# SolarMonitor.net
KiCad netlist of a schematic drawn in EAGLE
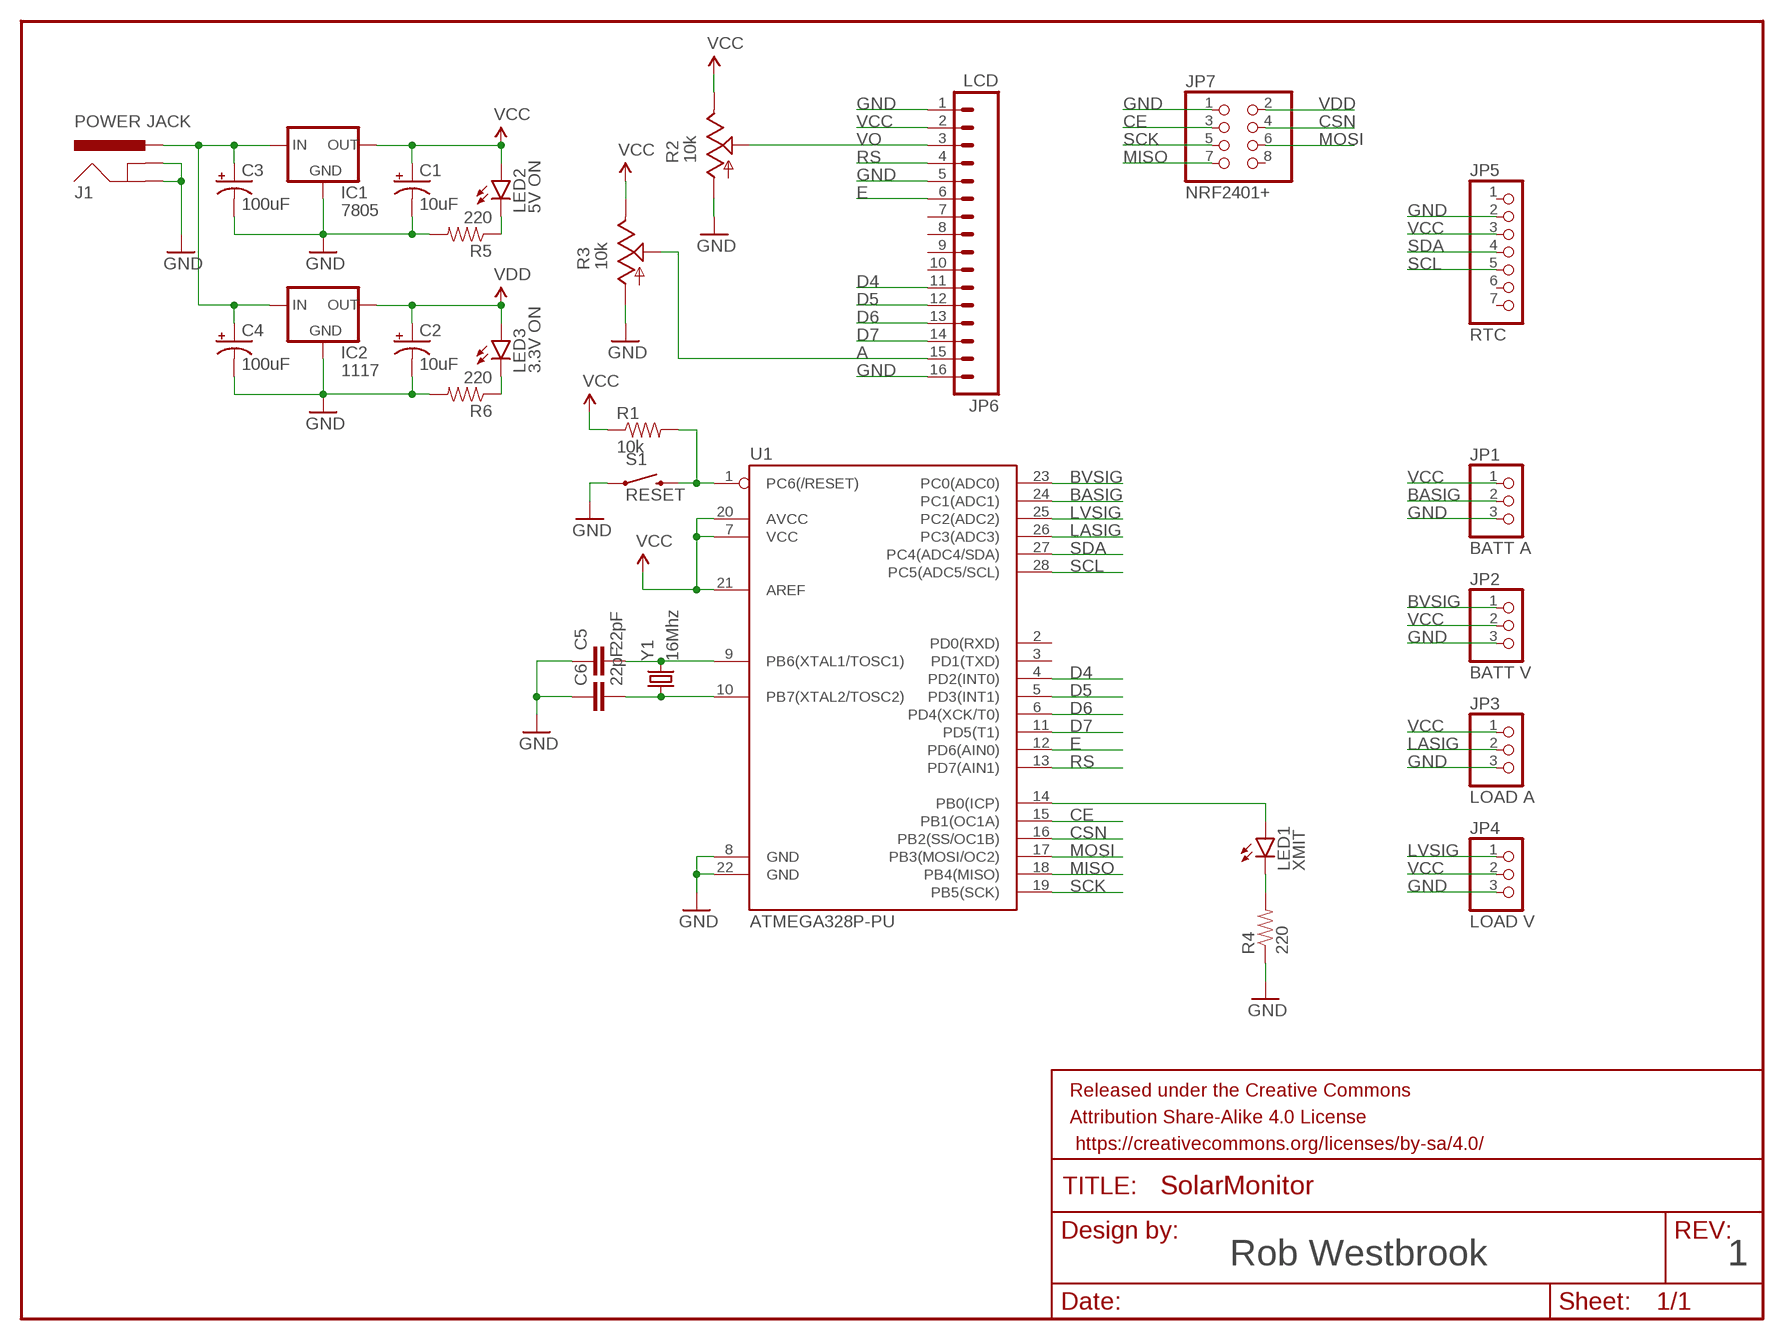
[diagram p0: schematic, sheet 1]

(export (version "E")
  (design (tool "Eeschema 10.0.6"))
  (components
    (comp (ref "C1")
      (value "10uF")
      (footprint "eagle-import:CPOL-RADIAL-100UF-25V")
      (libsource (lib "eagle-import") (part "CAP_POLPTH1"))
    )
    (comp (ref "C2")
      (value "10uF")
      (footprint "eagle-import:CPOL-RADIAL-100UF-25V")
      (libsource (lib "eagle-import") (part "CAP_POLPTH1"))
    )
    (comp (ref "C3")
      (value "100uF")
      (footprint "eagle-import:CPOL-RADIAL-10UF-25V")
      (libsource (lib "eagle-import") (part "CAP_POLPTH2"))
    )
    (comp (ref "C4")
      (value "100uF")
      (footprint "eagle-import:CPOL-RADIAL-10UF-25V")
      (libsource (lib "eagle-import") (part "CAP_POLPTH2"))
    )
    (comp (ref "C5")
      (value "22pF")
      (footprint "eagle-import:CAP-PTH-SMALLEZ")
      (libsource (lib "eagle-import") (part "CAPEZ"))
    )
    (comp (ref "C6")
      (value "22pF")
      (footprint "eagle-import:CAP-PTH-SMALLEZ")
      (libsource (lib "eagle-import") (part "CAPEZ"))
    )
    (comp (ref "FRAME1")
      (value "FRAME-LETTER")
      (footprint "eagle-import:CREATIVE_COMMONS")
      (libsource (lib "eagle-import") (part "FRAME-LETTER"))
    )
    (comp (ref "IC1")
      (value "7805")
      (footprint "eagle-import:TO-220-ALT")
      (libsource (lib "eagle-import") (part "V_REG_78XX-TO-220"))
    )
    (comp (ref "IC2")
      (value "1117")
      (footprint "eagle-import:78XXL")
      (libsource (lib "eagle-import") (part "V_REG_LD1117VXX"))
    )
    (comp (ref "J1")
      (value "POWER JACK")
      (footprint "eagle-import:POWER_JACK_PTH")
      (libsource (lib "eagle-import") (part "POWER_JACKPTH"))
    )
    (comp (ref "JP1")
      (value "BATT A")
      (footprint "eagle-import:1X03")
      (libsource (lib "eagle-import") (part "PINHD-1X3"))
    )
    (comp (ref "JP2")
      (value "BATT V")
      (footprint "eagle-import:1X03")
      (libsource (lib "eagle-import") (part "PINHD-1X3"))
    )
    (comp (ref "JP3")
      (value "LOAD A")
      (footprint "eagle-import:1X03")
      (libsource (lib "eagle-import") (part "PINHD-1X3"))
    )
    (comp (ref "JP4")
      (value "LOAD V")
      (footprint "eagle-import:1X03")
      (libsource (lib "eagle-import") (part "PINHD-1X3"))
    )
    (comp (ref "JP5")
      (value "RTC")
      (footprint "eagle-import:1X07")
      (libsource (lib "eagle-import") (part "PINHD-1X7"))
    )
    (comp (ref "JP6")
      (value "LCD")
      (footprint "eagle-import:1X16_LOCK")
      (libsource (lib "eagle-import") (part "M16LOCK"))
    )
    (comp (ref "JP7")
      (value "NRF2401+")
      (footprint "eagle-import:2X04")
      (libsource (lib "eagle-import") (part "PINHD-2X4"))
    )
    (comp (ref "LED1")
      (value "XMIT")
      (footprint "eagle-import:LED5MM")
      (libsource (lib "eagle-import") (part "LED5MM"))
    )
    (comp (ref "LED2")
      (value "5V ON")
      (footprint "eagle-import:LED5MM")
      (libsource (lib "eagle-import") (part "LED5MM"))
    )
    (comp (ref "LED3")
      (value "3.3V ON")
      (footprint "eagle-import:LED5MM")
      (libsource (lib "eagle-import") (part "LED5MM"))
    )
    (comp (ref "R1")
      (value "10k")
      (footprint "eagle-import:AXIAL-0.4")
      (libsource (lib "eagle-import") (part "RESISTORPTH-1/4W"))
    )
    (comp (ref "R2")
      (value "10k")
      (footprint "eagle-import:S64W")
      (libsource (lib "eagle-import") (part "TRIM_US-S64W"))
    )
    (comp (ref "R3")
      (value "10k")
      (footprint "eagle-import:S64W")
      (libsource (lib "eagle-import") (part "TRIM_US-S64W"))
    )
    (comp (ref "R4")
      (value "220")
      (footprint "eagle-import:AXIAL-0.4")
      (libsource (lib "eagle-import") (part "RESISTORPTH-1/4W"))
    )
    (comp (ref "R5")
      (value "220")
      (footprint "eagle-import:AXIAL-0.4")
      (libsource (lib "eagle-import") (part "RESISTORPTH-1/4W"))
    )
    (comp (ref "R6")
      (value "220")
      (footprint "eagle-import:AXIAL-0.4")
      (libsource (lib "eagle-import") (part "RESISTORPTH-1/4W"))
    )
    (comp (ref "S1")
      (value "RESET")
      (footprint "eagle-import:TACTILE-PTH")
      (libsource (lib "eagle-import") (part "SWITCH-MOMENTARY-2PTH"))
    )
    (comp (ref "U1")
      (value "ATMEGA328P-PU")
      (footprint "eagle-import:DIL28-3")
      (libsource (lib "eagle-import") (part "ATMEGA328P_PDIP"))
    )
    (comp (ref "Y1")
      (value "16Mhz")
      (footprint "eagle-import:HC49US")
      (libsource (lib "eagle-import") (part "CRYSTALHC49US"))
    )
  )
  (nets
    (net (code "1") (name "/A") (class "Default")
      (node (ref "JP6") (pin "15") (pinfunction "15_15") (pintype "passive"))
      (node (ref "R3") (pin "S") (pinfunction "S_S") (pintype "passive"))
    )
    (net (code "2") (name "/BASIG") (class "Default")
      (node (ref "JP1") (pin "2") (pinfunction "2_2") (pintype "passive"))
      (node (ref "U1") (pin "24") (pinfunction "PC1(ADC1)_24") (pintype "bidirectional"))
    )
    (net (code "3") (name "/BVSIG") (class "Default")
      (node (ref "JP2") (pin "1") (pinfunction "1_1") (pintype "passive"))
      (node (ref "U1") (pin "23") (pinfunction "PC0(ADC0)_23") (pintype "bidirectional"))
    )
    (net (code "4") (name "/CE") (class "Default")
      (node (ref "JP7") (pin "3") (pinfunction "3_3") (pintype "passive"))
      (node (ref "U1") (pin "15") (pinfunction "PB1(OC1A)_15") (pintype "bidirectional"))
    )
    (net (code "5") (name "/CSN") (class "Default")
      (node (ref "JP7") (pin "4") (pinfunction "4_4") (pintype "passive"))
      (node (ref "U1") (pin "16") (pinfunction "PB2(SS/OC1B)_16") (pintype "bidirectional"))
    )
    (net (code "6") (name "/D4") (class "Default")
      (node (ref "JP6") (pin "11") (pinfunction "11_11") (pintype "passive"))
      (node (ref "U1") (pin "4") (pinfunction "PD2(INT0)_4") (pintype "bidirectional"))
    )
    (net (code "7") (name "/D5") (class "Default")
      (node (ref "JP6") (pin "12") (pinfunction "12_12") (pintype "passive"))
      (node (ref "U1") (pin "5") (pinfunction "PD3(INT1)_5") (pintype "bidirectional"))
    )
    (net (code "8") (name "/D6") (class "Default")
      (node (ref "JP6") (pin "13") (pinfunction "13_13") (pintype "passive"))
      (node (ref "U1") (pin "6") (pinfunction "PD4(XCK/T0)_6") (pintype "bidirectional"))
    )
    (net (code "9") (name "/D7") (class "Default")
      (node (ref "JP6") (pin "14") (pinfunction "14_14") (pintype "passive"))
      (node (ref "U1") (pin "11") (pinfunction "PD5(T1)_11") (pintype "bidirectional"))
    )
    (net (code "10") (name "/E") (class "Default")
      (node (ref "JP6") (pin "6") (pinfunction "6_6") (pintype "passive"))
      (node (ref "U1") (pin "12") (pinfunction "PD6(AIN0)_12") (pintype "bidirectional"))
    )
    (net (code "11") (name "/LASIG") (class "Default")
      (node (ref "JP3") (pin "2") (pinfunction "2_2") (pintype "passive"))
      (node (ref "U1") (pin "26") (pinfunction "PC3(ADC3)_26") (pintype "bidirectional"))
    )
    (net (code "12") (name "/LVSIG") (class "Default")
      (node (ref "JP4") (pin "1") (pinfunction "1_1") (pintype "passive"))
      (node (ref "U1") (pin "25") (pinfunction "PC2(ADC2)_25") (pintype "bidirectional"))
    )
    (net (code "13") (name "/MISO") (class "Default")
      (node (ref "JP7") (pin "7") (pinfunction "7_7") (pintype "passive"))
      (node (ref "U1") (pin "18") (pinfunction "PB4(MISO)_18") (pintype "bidirectional"))
    )
    (net (code "14") (name "/MOSI") (class "Default")
      (node (ref "JP7") (pin "6") (pinfunction "6_6") (pintype "passive"))
      (node (ref "U1") (pin "17") (pinfunction "PB3(MOSI/OC2)_17") (pintype "bidirectional"))
    )
    (net (code "15") (name "/RS") (class "Default")
      (node (ref "JP6") (pin "4") (pinfunction "4_4") (pintype "passive"))
      (node (ref "U1") (pin "13") (pinfunction "PD7(AIN1)_13") (pintype "bidirectional"))
    )
    (net (code "16") (name "/SCK") (class "Default")
      (node (ref "JP7") (pin "5") (pinfunction "5_5") (pintype "passive"))
      (node (ref "U1") (pin "19") (pinfunction "PB5(SCK)_19") (pintype "bidirectional"))
    )
    (net (code "17") (name "/SCL") (class "Default")
      (node (ref "JP5") (pin "5") (pinfunction "5_5") (pintype "passive"))
      (node (ref "U1") (pin "28") (pinfunction "PC5(ADC5/SCL)_28") (pintype "bidirectional"))
    )
    (net (code "18") (name "/SDA") (class "Default")
      (node (ref "JP5") (pin "4") (pinfunction "4_4") (pintype "passive"))
      (node (ref "U1") (pin "27") (pinfunction "PC4(ADC4/SDA)_27") (pintype "bidirectional"))
    )
    (net (code "19") (name "/VO") (class "Default")
      (node (ref "JP6") (pin "3") (pinfunction "3_3") (pintype "passive"))
      (node (ref "R2") (pin "S") (pinfunction "S_S") (pintype "passive"))
    )
    (net (code "20") (name "GND") (class "Default")
      (node (ref "C1") (pin "2") (pinfunction "-_2") (pintype "passive"))
      (node (ref "C2") (pin "2") (pinfunction "-_2") (pintype "passive"))
      (node (ref "C3") (pin "2") (pinfunction "-_2") (pintype "passive"))
      (node (ref "C4") (pin "2") (pinfunction "-_2") (pintype "passive"))
      (node (ref "C5") (pin "1") (pinfunction "1_1") (pintype "passive"))
      (node (ref "C6") (pin "1") (pinfunction "1_1") (pintype "passive"))
      (node (ref "IC1") (pin "GND") (pinfunction "GND_GND") (pintype "input"))
      (node (ref "IC2") (pin "IN") (pinfunction "GND_IN") (pintype "input"))
      (node (ref "J1") (pin "GND") (pinfunction "GND_GND") (pintype "bidirectional"))
      (node (ref "J1") (pin "GNDBREAK") (pinfunction "GNDBREAK_GNDBREAK") (pintype "bidirectional"))
      (node (ref "JP1") (pin "3") (pinfunction "3_3") (pintype "passive"))
      (node (ref "JP2") (pin "3") (pinfunction "3_3") (pintype "passive"))
      (node (ref "JP3") (pin "3") (pinfunction "3_3") (pintype "passive"))
      (node (ref "JP4") (pin "3") (pinfunction "3_3") (pintype "passive"))
      (node (ref "JP5") (pin "2") (pinfunction "2_2") (pintype "passive"))
      (node (ref "JP6") (pin "1") (pinfunction "1_1") (pintype "passive"))
      (node (ref "JP6") (pin "16") (pinfunction "16_16") (pintype "passive"))
      (node (ref "JP6") (pin "5") (pinfunction "5_5") (pintype "passive"))
      (node (ref "JP7") (pin "1") (pinfunction "1_1") (pintype "passive"))
      (node (ref "R2") (pin "A") (pinfunction "A_A") (pintype "passive"))
      (node (ref "R3") (pin "A") (pinfunction "A_A") (pintype "passive"))
      (node (ref "R4") (pin "P$1") (pinfunction "1_P$1") (pintype "passive"))
      (node (ref "R5") (pin "P$2") (pinfunction "2_P$2") (pintype "passive"))
      (node (ref "R6") (pin "P$2") (pinfunction "2_P$2") (pintype "passive"))
      (node (ref "S1") (pin "1") (pinfunction "1_1") (pintype "passive"))
      (node (ref "U1") (pin "22") (pinfunction "GND_22") (pintype "bidirectional"))
      (node (ref "U1") (pin "8") (pinfunction "GND_8") (pintype "bidirectional"))
    )
    (net (code "21") (name "Net-(C3-+)") (class "Default")
      (node (ref "C3") (pin "1") (pinfunction "+_1") (pintype "passive"))
      (node (ref "C4") (pin "1") (pinfunction "+_1") (pintype "passive"))
      (node (ref "IC1") (pin "IN") (pinfunction "IN_IN") (pintype "input"))
      (node (ref "IC2") (pin "OUT") (pinfunction "IN_OUT") (pintype "input"))
      (node (ref "J1") (pin "PWR") (pinfunction "PWR_PWR") (pintype "bidirectional"))
    )
    (net (code "22") (name "Net-(LED1-C)") (class "Default")
      (node (ref "LED1") (pin "K") (pinfunction "C_K") (pintype "passive"))
      (node (ref "R4") (pin "P$2") (pinfunction "2_P$2") (pintype "passive"))
    )
    (net (code "23") (name "Net-(LED2-C)") (class "Default")
      (node (ref "LED2") (pin "K") (pinfunction "C_K") (pintype "passive"))
      (node (ref "R5") (pin "P$1") (pinfunction "1_P$1") (pintype "passive"))
    )
    (net (code "24") (name "Net-(LED3-C)") (class "Default")
      (node (ref "LED3") (pin "K") (pinfunction "C_K") (pintype "passive"))
      (node (ref "R6") (pin "P$1") (pinfunction "1_P$1") (pintype "passive"))
    )
    (net (code "25") (name "Net-(R1-2)") (class "Default")
      (node (ref "R1") (pin "P$2") (pinfunction "2_P$2") (pintype "passive"))
      (node (ref "S1") (pin "3") (pinfunction "2_3") (pintype "passive"))
      (node (ref "U1") (pin "1") (pinfunction "PC6(/RESET)_1") (pintype "bidirectional"))
    )
    (net (code "26") (name "Net-(U1-PB0(ICP))") (class "Default")
      (node (ref "LED1") (pin "A") (pinfunction "A_A") (pintype "passive"))
      (node (ref "U1") (pin "14") (pinfunction "PB0(ICP)_14") (pintype "bidirectional"))
    )
    (net (code "27") (name "Net-(U1-PB6(XTAL1{slash}TOSC1))") (class "Default")
      (node (ref "C5") (pin "2") (pinfunction "2_2") (pintype "passive"))
      (node (ref "U1") (pin "9") (pinfunction "PB6(XTAL1/TOSC1)_9") (pintype "bidirectional"))
      (node (ref "Y1") (pin "2") (pinfunction "2_2") (pintype "passive"))
    )
    (net (code "28") (name "Net-(U1-PB7(XTAL2{slash}TOSC2))") (class "Default")
      (node (ref "C6") (pin "2") (pinfunction "2_2") (pintype "passive"))
      (node (ref "U1") (pin "10") (pinfunction "PB7(XTAL2/TOSC2)_10") (pintype "bidirectional"))
      (node (ref "Y1") (pin "1") (pinfunction "1_1") (pintype "passive"))
    )
    (net (code "29") (name "VCC") (class "Default")
      (node (ref "C1") (pin "1") (pinfunction "+_1") (pintype "passive"))
      (node (ref "IC1") (pin "OUT") (pinfunction "OUT_OUT") (pintype "output"))
      (node (ref "JP1") (pin "1") (pinfunction "1_1") (pintype "passive"))
      (node (ref "JP2") (pin "2") (pinfunction "2_2") (pintype "passive"))
      (node (ref "JP3") (pin "1") (pinfunction "1_1") (pintype "passive"))
      (node (ref "JP4") (pin "2") (pinfunction "2_2") (pintype "passive"))
      (node (ref "JP5") (pin "3") (pinfunction "3_3") (pintype "passive"))
      (node (ref "JP6") (pin "2") (pinfunction "2_2") (pintype "passive"))
      (node (ref "LED2") (pin "A") (pinfunction "A_A") (pintype "passive"))
      (node (ref "R1") (pin "P$1") (pinfunction "1_P$1") (pintype "passive"))
      (node (ref "R2") (pin "E") (pinfunction "E_E") (pintype "passive"))
      (node (ref "R3") (pin "E") (pinfunction "E_E") (pintype "passive"))
      (node (ref "U1") (pin "20") (pinfunction "AVCC_20") (pintype "bidirectional"))
      (node (ref "U1") (pin "21") (pinfunction "AREF_21") (pintype "bidirectional"))
      (node (ref "U1") (pin "7") (pinfunction "VCC_7") (pintype "bidirectional"))
    )
    (net (code "30") (name "VDD") (class "Default")
      (node (ref "C2") (pin "1") (pinfunction "+_1") (pintype "passive"))
      (node (ref "IC2") (pin "GND") (pinfunction "OUT_GND") (pintype "output"))
      (node (ref "JP7") (pin "2") (pinfunction "2_2") (pintype "passive"))
      (node (ref "LED3") (pin "A") (pinfunction "A_A") (pintype "passive"))
    )
    (net (code "31") (name "unconnected-(JP5-Pad1)") (class "Default")
      (node (ref "JP5") (pin "1") (pinfunction "1_1") (pintype "passive"))
    )
    (net (code "32") (name "unconnected-(JP5-Pad6)") (class "Default")
      (node (ref "JP5") (pin "6") (pinfunction "6_6") (pintype "passive"))
    )
    (net (code "33") (name "unconnected-(JP5-Pad7)") (class "Default")
      (node (ref "JP5") (pin "7") (pinfunction "7_7") (pintype "passive"))
    )
    (net (code "34") (name "unconnected-(JP6-Pad7)") (class "Default")
      (node (ref "JP6") (pin "7") (pinfunction "7_7") (pintype "passive"))
    )
    (net (code "35") (name "unconnected-(JP6-Pad8)") (class "Default")
      (node (ref "JP6") (pin "8") (pinfunction "8_8") (pintype "passive"))
    )
    (net (code "36") (name "unconnected-(JP6-Pad9)") (class "Default")
      (node (ref "JP6") (pin "9") (pinfunction "9_9") (pintype "passive"))
    )
    (net (code "37") (name "unconnected-(JP6-Pad10)") (class "Default")
      (node (ref "JP6") (pin "10") (pinfunction "10_10") (pintype "passive"))
    )
    (net (code "38") (name "unconnected-(JP7-Pad8)") (class "Default")
      (node (ref "JP7") (pin "8") (pinfunction "8_8") (pintype "passive"))
    )
    (net (code "39") (name "unconnected-(U1-PD0(RXD)-Pad2)") (class "Default")
      (node (ref "U1") (pin "2") (pinfunction "PD0(RXD)_2") (pintype "bidirectional"))
    )
    (net (code "40") (name "unconnected-(U1-PD1(TXD)-Pad3)") (class "Default")
      (node (ref "U1") (pin "3") (pinfunction "PD1(TXD)_3") (pintype "bidirectional"))
    )
  )
)
